# UCPD_lamp.net
KiCad netlist of a schematic drawn in Altium Designer
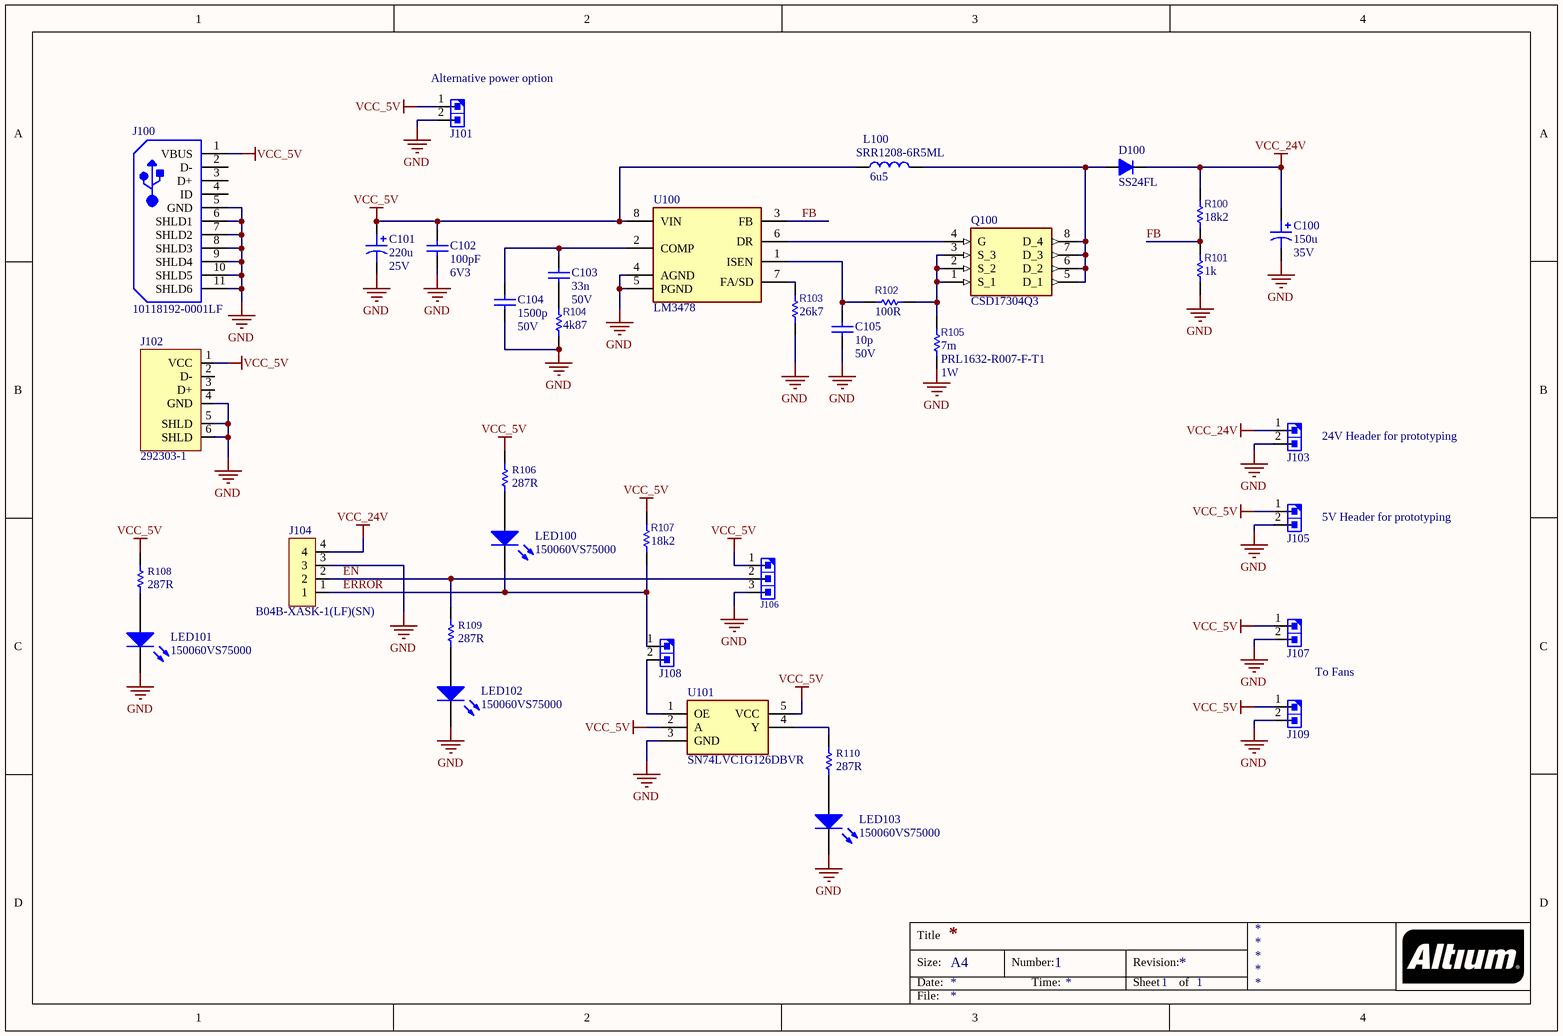
[diagram p0: UCPD_lamp.SchDoc]

(export (version "E")
  (design (tool "Eeschema 10.0.6"))
  (components
    (comp (ref "C100")
      (value "150u")
      (footprint "CAPAE1030X1050N")
      (description "CAP ALUM POLY HYB 150UF 35V SMD")
      (fields
        (field (name "MANUFACTURER") "Panasonic")
        (field (name "MANUFACTURER PART NUMBER") "EEH-ZA1V151P")
        (field (name "VOLTAGE") "35V")
      )
      (libsource (lib "UCPD_capacitors") (part "EEH-ZA1V151P"))
    )
    (comp (ref "C101")
      (value "220u")
      (footprint "CAPAE1030X1050N")
      (description "CAP ALUM 220UF 20% 25V SMD")
      (fields
        (field (name "MANUFACTURER") "Nichicon")
        (field (name "MANUFACTURER PART NUMBER") "UUD1E221MNL1GS")
        (field (name "VOLTAGE") "25V")
      )
      (libsource (lib "UCPD_capacitors") (part "UUD1E221MNL1GS"))
    )
    (comp (ref "C102")
      (value "100pF")
      (footprint "CAPC1005X06N")
      (description "CAP CER 0.1UF 6.3V X7R 0402")
      (fields
        (field (name "MANUFACTURER PART NUMBER") "GRM155R70J104KA01D")
        (field (name "MANUFACTURER") "Murata")
        (field (name "VOLTAGE") "6V3")
      )
      (libsource (lib "UCPD_capacitors") (part "GRM155R70J104KA01D"))
    )
    (comp (ref "C103")
      (value "33n")
      (footprint "CAPC2012X14N")
      (description "CAP CER 0.033UF 50V C0G 0805")
      (fields
        (field (name "MANUFACTURER PART NUMBER") "CGA4J2C0G1H333J125AA")
        (field (name "MANUFACTURER") "TDK")
        (field (name "VOLTAGE") "50V")
      )
      (libsource (lib "UCPD_capacitors") (part "CGA4J2C0G1H333J125AA"))
    )
    (comp (ref "C104")
      (value "1500p")
      (footprint "CAPC2012X14N")
      (description "CAP CER 1500PF 50V C0G 0805")
      (fields
        (field (name "MANUFACTURER PART NUMBER") "C2012C0G1H152J060AA")
        (field (name "MANUFACTURER") "TDK")
        (field (name "VOLTAGE") "50V")
      )
      (libsource (lib "UCPD_capacitors") (part "C2012C0G1H152J060AA"))
    )
    (comp (ref "C105")
      (value "10p")
      (footprint "CAPC2012X14N")
      (description "CAP CER 10PF 50V C0G/NP0 0805")
      (fields
        (field (name "MANUFACTURER PART NUMBER") "08055A100JAT2A")
        (field (name "MANUFACTURER") "AVX")
        (field (name "VOLTAGE") "50V")
      )
      (libsource (lib "UCPD_capacitors") (part "08055A100JAT2A"))
    )
    (comp (ref "D100")
      (value "SS24FL")
      (footprint "SOD-123FL")
      (description "DIODE SCHOTTKY 40V 2A SOD123F")
      (fields (field (name "MANUFACTURER") "ON Semiconductor"))
      (libsource (lib "UCPD") (part "SS24FL"))
    )
    (comp (ref "J100")
      (value "10118192-0001LF")
      (footprint "10118192-0001LF")
      (description "CONN Micro USB B Type Receptacle")
      (fields (field (name "MANUFACTURER") "FCI"))
      (libsource (lib "UCPD") (part "10118192-0001LF"))
    )
    (comp (ref "J101")
      (value "PRPC002SAAN-RC")
      (footprint "HDR_1x2_0.100\"")
      (description "CONN HEADER VERT 2POS 2.54MM")
      (fields (field (name "MANUFACTURER") "Sullins"))
      (libsource (lib "UCPD") (part "PRPC002SAAN-RC"))
    )
    (comp (ref "J102")
      (value "292303-1")
      (footprint "292303-1")
      (description "CONN USB2.0 TYPEA 4POS R/A")
      (fields (field (name "MANUFACTURER") "TE Connectivity"))
      (libsource (lib "UCPD") (part "292303-1"))
    )
    (comp (ref "J103")
      (value "PRPC002SAAN-RC")
      (footprint "HDR_1x2_0.100\"")
      (description "CONN HEADER VERT 2POS 2.54MM")
      (fields (field (name "MANUFACTURER") "Sullins"))
      (libsource (lib "UCPD") (part "PRPC002SAAN-RC"))
    )
    (comp (ref "J104")
      (value "B04B-XASK-1(LF)(SN)")
      (footprint "B04B-XASK-1(LF)(SN)")
      (description "CONN HEADER VERT 4POS 2.5MM")
      (fields (field (name "MANUFACTURER") "JST"))
      (libsource (lib "UCPD") (part "B04B-XASK-1(LF)(SN)"))
    )
    (comp (ref "J105")
      (value "PRPC002SAAN-RC")
      (footprint "HDR_1x2_0.100\"")
      (description "CONN HEADER VERT 2POS 2.54MM")
      (fields (field (name "MANUFACTURER") "Sullins"))
      (libsource (lib "UCPD") (part "PRPC002SAAN-RC"))
    )
    (comp (ref "J106")
      (value "PRPC003SAAN-RC")
      (footprint "HDR 3x1 0.100\"")
      (description "CONN HEADER VERT 3POS 2.54MM")
      (fields (field (name "MANUFACTURER") "Sullins"))
      (libsource (lib "UCPD") (part "PRPC003SAAN-RC"))
    )
    (comp (ref "J107")
      (value "PRPC002SAAN-RC")
      (footprint "HDR_1x2_0.100\"")
      (description "CONN HEADER VERT 2POS 2.54MM")
      (fields (field (name "MANUFACTURER") "Sullins"))
      (libsource (lib "UCPD") (part "PRPC002SAAN-RC"))
    )
    (comp (ref "J108")
      (value "PRPC002SAAN-RC")
      (footprint "HDR_1x2_0.100\"")
      (description "CONN HEADER VERT 2POS 2.54MM")
      (fields (field (name "MANUFACTURER") "Sullins"))
      (libsource (lib "UCPD") (part "PRPC002SAAN-RC"))
    )
    (comp (ref "J109")
      (value "PRPC002SAAN-RC")
      (footprint "HDR_1x2_0.100\"")
      (description "CONN HEADER VERT 2POS 2.54MM")
      (fields (field (name "MANUFACTURER") "Sullins"))
      (libsource (lib "UCPD") (part "PRPC002SAAN-RC"))
    )
    (comp (ref "L100")
      (value "6u5")
      (footprint "INDPM127127X850N")
      (description "FIXED IND 6.5UH 6A 18 MOHM SMD")
      (fields
        (field (name "MANUFACTURER") "Bourns")
        (field (name "MANUFACTURER PART NUMBER") "SRR1208-6R5ML")
        (field (name "Comment") "SRR1208-6R5ML")
      )
      (libsource (lib "UCPD") (part "SRR1208-6R5ML"))
    )
    (comp (ref "LED100")
      (value "150060VS75000")
      (footprint "0603_A")
      (description "SMD mono-color Chip LED, WL-SMCW, Bright Green")
      (fields
        (field (name "MANUFACTURER") "Wuerth Elektronik")
        (field (name "DISTRIBUTOR PART NUMBER") "732-4980-1-ND")
      )
      (libsource (lib "Altium Content Vault") (part "WE-LED_K1A2-2"))
    )
    (comp (ref "LED101")
      (value "150060VS75000")
      (footprint "0603_A")
      (description "SMD mono-color Chip LED, WL-SMCW, Bright Green")
      (fields
        (field (name "MANUFACTURER") "Wuerth Elektronik")
        (field (name "DISTRIBUTOR PART NUMBER") "732-4980-1-ND")
      )
      (libsource (lib "Altium Content Vault") (part "WE-LED_K1A2-2"))
    )
    (comp (ref "LED102")
      (value "150060VS75000")
      (footprint "0603_A")
      (description "SMD mono-color Chip LED, WL-SMCW, Bright Green")
      (fields
        (field (name "MANUFACTURER") "Wuerth Elektronik")
        (field (name "DISTRIBUTOR PART NUMBER") "732-4980-1-ND")
      )
      (libsource (lib "Altium Content Vault") (part "WE-LED_K1A2-2"))
    )
    (comp (ref "LED103")
      (value "150060VS75000")
      (footprint "0603_A")
      (description "SMD mono-color Chip LED, WL-SMCW, Bright Green")
      (fields
        (field (name "MANUFACTURER") "Wuerth Elektronik")
        (field (name "DISTRIBUTOR PART NUMBER") "732-4980-1-ND")
      )
      (libsource (lib "Altium Content Vault") (part "WE-LED_K1A2-2"))
    )
    (comp (ref "Q100")
      (value "CSD17304Q3")
      (footprint "SamacSys:DQG_VSON-CLIP")
      (description "MOSFET (N-Channel)")
      (fields (field (name "MOUSER PART NUMBER") "595-CSD17304Q3"))
      (libsource (lib "*") (part "CSD17304Q3"))
    )
    (comp (ref "R100")
      (value "18k2")
      (footprint "RESC1005X03N")
      (description "RES SMD 18.2K OHM 1% 1/16W 0402")
      (fields
        (field (name "MANUFACTURER") "Vishay Dale")
        (field (name "MANUFACTURER PART NUMBER") "CRCW040218K2FKED")
      )
      (libsource (lib "UCPD_resistors") (part "CRCW040218K2FKED"))
    )
    (comp (ref "R101")
      (value "1k")
      (footprint "RESC1005X03N")
      (description "RES SMD 1K OHM 1% 1/16W 0402")
      (fields
        (field (name "MANUFACTURER") "Vishay Dale")
        (field (name "MANUFACTURER PART NUMBER") "CRCW04021K00FKEDC")
      )
      (libsource (lib "UCPD_resistors") (part "CRCW04021K00FKEDC"))
    )
    (comp (ref "R102")
      (value "100R")
      (footprint "RESC1005X03N")
      (description "RES SMD 100 OHM 1% 1/16W 0402")
      (fields
        (field (name "MANUFACTURER") "Vishay Dale")
        (field (name "MANUFACTURER PART NUMBER") "CRCW0402100RFKEDC")
      )
      (libsource (lib "UCPD_resistors") (part "CRCW0402100RFKEDC"))
    )
    (comp (ref "R103")
      (value "26k7")
      (footprint "RESC1005X03N")
      (description "RES SMD 26.7K OHM 1% 1/16W 0402")
      (fields
        (field (name "MANUFACTURER") "Vishay Dale")
        (field (name "MANUFACTURER PART NUMBER") "CRCW040226K7FKED")
      )
      (libsource (lib "UCPD_resistors") (part "CRCW040226K7FKED"))
    )
    (comp (ref "R104")
      (value "4k87")
      (footprint "RESC1005X03N")
      (description "RES SMD 4.87K OHM 1% 1/16W 0402")
      (fields
        (field (name "MANUFACTURER") "Vishay Dale")
        (field (name "MANUFACTURER PART NUMBER") "CRCW04024K87FKED")
      )
      (libsource (lib "UCPD_resistors") (part "CRCW04024K87FKED"))
    )
    (comp (ref "R105")
      (value "7m")
      (footprint "RESC1632X60N")
      (description "RES 0.007 OHM 1W 1206 WIDE")
      (fields
        (field (name "MANUFACTURER") "Susumu")
        (field (name "MANUFACTURER PART NUMBER") "PRL1632-R007-F-T1")
        (field (name "POWER") "1W")
        (field (name "Comment") "PRL1632-R007-F-T1")
      )
      (libsource (lib "UCPD_resistors") (part "PRL1632-R007-F-T1"))
    )
    (comp (ref "R106")
      (value "287R")
      (footprint "RESC1005X03N")
      (fields
        (field (name "MANUFACTURER") "Yageo")
        (field (name "MANUFACTURER PART NUMBER") "YAG3089CT-ND")
        (field (name "Comment") "RES: GENERAL")
      )
      (libsource (lib "UCPD_resistors") (part "RES{colon} GENERAL"))
    )
    (comp (ref "R107")
      (value "18k2")
      (footprint "RESC1005X03N")
      (description "RES SMD 18.2K OHM 1% 1/16W 0402")
      (fields
        (field (name "MANUFACTURER") "Vishay Dale")
        (field (name "MANUFACTURER PART NUMBER") "CRCW040218K2FKED")
      )
      (libsource (lib "UCPD_resistors") (part "CRCW040218K2FKED"))
    )
    (comp (ref "R108")
      (value "287R")
      (footprint "RESC1005X03N")
      (fields
        (field (name "MANUFACTURER") "Yageo")
        (field (name "MANUFACTURER PART NUMBER") "YAG3089CT-ND")
        (field (name "Comment") "RES: GENERAL")
      )
      (libsource (lib "UCPD_resistors") (part "RES{colon} GENERAL"))
    )
    (comp (ref "R109")
      (value "287R")
      (footprint "RESC1005X03N")
      (fields
        (field (name "MANUFACTURER") "Yageo")
        (field (name "MANUFACTURER PART NUMBER") "YAG3089CT-ND")
        (field (name "Comment") "RES: GENERAL")
      )
      (libsource (lib "UCPD_resistors") (part "RES{colon} GENERAL"))
    )
    (comp (ref "R110")
      (value "287R")
      (footprint "RESC1005X03N")
      (fields
        (field (name "MANUFACTURER") "Yageo")
        (field (name "MANUFACTURER PART NUMBER") "YAG3089CT-ND")
        (field (name "Comment") "RES: GENERAL")
      )
      (libsource (lib "UCPD_resistors") (part "RES{colon} GENERAL"))
    )
    (comp (ref "U100")
      (value "LM3478")
      (footprint "SOIC127P600X175-8N")
      (description "IC REG CTRLR MULT TOPOLOGY 8SOIC")
      (fields
        (field (name "MANUFACTURER") "Texas Instruments")
        (field (name "MANUFACTURER PART NUMBER") "LM3478MAX/NOPB")
      )
      (libsource (lib "UCPD") (part "LM3478"))
    )
    (comp (ref "U101")
      (value "SN74LVC1G126DBVR")
      (footprint "SOT95P280X145-5N")
      (description "IC BUF NON-INVERT 5.5V SOT23-5")
      (fields
        (field (name "MANUFACTURER") "Texas Instruments")
        (field (name "MOUSER PART NUMBER") "595-SN74LVC1G126DBVR")
      )
      (libsource (lib "UCPD") (part "SN74LVC1G126DBVR"))
    )
  )
  (nets
    (net (code "1") (name "/EN") (class "Default")
      (node (ref "J104") (pin "2") (pinfunction "2_2") (pintype "passive"))
      (node (ref "J106") (pin "2") (pinfunction "2_2") (pintype "passive"))
      (node (ref "R109") (pin "2") (pinfunction "2_2") (pintype "passive"))
    )
    (net (code "2") (name "/ERROR") (class "Default")
      (node (ref "J104") (pin "1") (pinfunction "1_1") (pintype "passive"))
      (node (ref "J108") (pin "1") (pinfunction "1_1") (pintype "passive"))
      (node (ref "LED100") (pin "1") (pinfunction "K_1") (pintype "passive"))
      (node (ref "R107") (pin "1") (pinfunction "1_1") (pintype "passive"))
    )
    (net (code "3") (name "/FB") (class "Default")
      (node (ref "R100") (pin "1") (pinfunction "1_1") (pintype "passive"))
      (node (ref "R101") (pin "2") (pinfunction "2_2") (pintype "passive"))
      (node (ref "U100") (pin "3") (pinfunction "FB_3") (pintype "passive"))
    )
    (net (code "4") (name "GND") (class "Default")
      (node (ref "C100") (pin "2") (pinfunction "2_2") (pintype "passive"))
      (node (ref "C101") (pin "2") (pinfunction "2_2") (pintype "passive"))
      (node (ref "C102") (pin "1") (pinfunction "1_1") (pintype "passive"))
      (node (ref "C104") (pin "1") (pinfunction "1_1") (pintype "passive"))
      (node (ref "C105") (pin "1") (pinfunction "1_1") (pintype "passive"))
      (node (ref "J100") (pin "10") (pinfunction "SHLD5_10") (pintype "passive"))
      (node (ref "J100") (pin "11") (pinfunction "SHLD6_11") (pintype "passive"))
      (node (ref "J100") (pin "5") (pinfunction "GND_5") (pintype "passive"))
      (node (ref "J100") (pin "6") (pinfunction "SHLD1_6") (pintype "passive"))
      (node (ref "J100") (pin "7") (pinfunction "SHLD2_7") (pintype "passive"))
      (node (ref "J100") (pin "8") (pinfunction "SHLD3_8") (pintype "passive"))
      (node (ref "J100") (pin "9") (pinfunction "SHLD4_9") (pintype "passive"))
      (node (ref "J101") (pin "2") (pinfunction "2_2") (pintype "passive"))
      (node (ref "J102") (pin "4") (pinfunction "GND_4") (pintype "passive"))
      (node (ref "J102") (pin "5") (pinfunction "SHLD_5") (pintype "passive"))
      (node (ref "J102") (pin "6") (pinfunction "SHLD_6") (pintype "passive"))
      (node (ref "J103") (pin "2") (pinfunction "2_2") (pintype "passive"))
      (node (ref "J104") (pin "3") (pinfunction "3_3") (pintype "passive"))
      (node (ref "J105") (pin "2") (pinfunction "2_2") (pintype "passive"))
      (node (ref "J106") (pin "3") (pinfunction "3_3") (pintype "passive"))
      (node (ref "J107") (pin "2") (pinfunction "2_2") (pintype "passive"))
      (node (ref "J109") (pin "2") (pinfunction "2_2") (pintype "passive"))
      (node (ref "LED101") (pin "1") (pinfunction "K_1") (pintype "passive"))
      (node (ref "LED102") (pin "1") (pinfunction "K_1") (pintype "passive"))
      (node (ref "LED103") (pin "1") (pinfunction "K_1") (pintype "passive"))
      (node (ref "R101") (pin "1") (pinfunction "1_1") (pintype "passive"))
      (node (ref "R103") (pin "1") (pinfunction "1_1") (pintype "passive"))
      (node (ref "R104") (pin "1") (pinfunction "1_1") (pintype "passive"))
      (node (ref "R105") (pin "1") (pinfunction "1_1") (pintype "passive"))
      (node (ref "U100") (pin "4") (pinfunction "AGND_4") (pintype "passive"))
      (node (ref "U100") (pin "5") (pinfunction "PGND_5") (pintype "passive"))
      (node (ref "U101") (pin "3") (pinfunction "GND_3") (pintype "passive"))
    )
    (net (code "5") (name "Net-(C103-Pad1)") (class "Default")
      (node (ref "C103") (pin "1") (pinfunction "1_1") (pintype "passive"))
      (node (ref "R104") (pin "2") (pinfunction "2_2") (pintype "passive"))
    )
    (net (code "6") (name "Net-(D100-A)") (class "Default")
      (node (ref "D100") (pin "1") (pinfunction "A_1") (pintype "passive"))
      (node (ref "L100") (pin "2") (pinfunction "2_2") (pintype "passive"))
      (node (ref "Q100") (pin "5") (pinfunction "D_1_5") (pintype "output"))
      (node (ref "Q100") (pin "6") (pinfunction "D_2_6") (pintype "output"))
      (node (ref "Q100") (pin "7") (pinfunction "D_3_7") (pintype "output"))
      (node (ref "Q100") (pin "8") (pinfunction "D_4_8") (pintype "output"))
    )
    (net (code "7") (name "Net-(LED100-A)") (class "Default")
      (node (ref "LED100") (pin "2") (pinfunction "A_2") (pintype "passive"))
      (node (ref "R106") (pin "1") (pinfunction "1_1") (pintype "passive"))
    )
    (net (code "8") (name "Net-(LED101-A)") (class "Default")
      (node (ref "LED101") (pin "2") (pinfunction "A_2") (pintype "passive"))
      (node (ref "R108") (pin "1") (pinfunction "1_1") (pintype "passive"))
    )
    (net (code "9") (name "Net-(LED102-A)") (class "Default")
      (node (ref "LED102") (pin "2") (pinfunction "A_2") (pintype "passive"))
      (node (ref "R109") (pin "1") (pinfunction "1_1") (pintype "passive"))
    )
    (net (code "10") (name "Net-(LED103-A)") (class "Default")
      (node (ref "LED103") (pin "2") (pinfunction "A_2") (pintype "passive"))
      (node (ref "R110") (pin "1") (pinfunction "1_1") (pintype "passive"))
    )
    (net (code "11") (name "Net-(Q100-G)") (class "Default")
      (node (ref "Q100") (pin "4") (pinfunction "G_4") (pintype "input"))
      (node (ref "U100") (pin "6") (pinfunction "DR_6") (pintype "passive"))
    )
    (net (code "12") (name "Net-(Q100-S_1)") (class "Default")
      (node (ref "Q100") (pin "1") (pinfunction "S_1_1") (pintype "input"))
      (node (ref "Q100") (pin "2") (pinfunction "S_2_2") (pintype "input"))
      (node (ref "Q100") (pin "3") (pinfunction "S_3_3") (pintype "input"))
      (node (ref "R102") (pin "2") (pinfunction "2_2") (pintype "passive"))
      (node (ref "R105") (pin "2") (pinfunction "2_2") (pintype "passive"))
    )
    (net (code "13") (name "Net-(U100-COMP)") (class "Default")
      (node (ref "C103") (pin "2") (pinfunction "2_2") (pintype "passive"))
      (node (ref "C104") (pin "2") (pinfunction "2_2") (pintype "passive"))
      (node (ref "U100") (pin "2") (pinfunction "COMP_2") (pintype "passive"))
    )
    (net (code "14") (name "Net-(U100-FA{slash}SD)") (class "Default")
      (node (ref "R103") (pin "2") (pinfunction "2_2") (pintype "passive"))
      (node (ref "U100") (pin "7") (pinfunction "FA/SD_7") (pintype "passive"))
    )
    (net (code "15") (name "Net-(U100-ISEN)") (class "Default")
      (node (ref "C105") (pin "2") (pinfunction "2_2") (pintype "passive"))
      (node (ref "R102") (pin "1") (pinfunction "1_1") (pintype "passive"))
      (node (ref "U100") (pin "1") (pinfunction "ISEN_1") (pintype "passive"))
    )
    (net (code "16") (name "Net-(U101-OE)") (class "Default")
      (node (ref "J108") (pin "2") (pinfunction "2_2") (pintype "passive"))
      (node (ref "U101") (pin "1") (pinfunction "OE_1") (pintype "passive"))
    )
    (net (code "17") (name "Net-(U101-Y)") (class "Default")
      (node (ref "R110") (pin "2") (pinfunction "2_2") (pintype "passive"))
      (node (ref "U101") (pin "4") (pinfunction "Y_4") (pintype "passive"))
    )
    (net (code "18") (name "VCC_5V") (class "Default")
      (node (ref "C101") (pin "1") (pinfunction "1_1") (pintype "passive"))
      (node (ref "C102") (pin "2") (pinfunction "2_2") (pintype "passive"))
      (node (ref "J100") (pin "1") (pinfunction "VBUS_1") (pintype "passive"))
      (node (ref "J101") (pin "1") (pinfunction "1_1") (pintype "passive"))
      (node (ref "J102") (pin "1") (pinfunction "VCC_1") (pintype "passive"))
      (node (ref "J105") (pin "1") (pinfunction "1_1") (pintype "passive"))
      (node (ref "J106") (pin "1") (pinfunction "1_1") (pintype "passive"))
      (node (ref "J107") (pin "1") (pinfunction "1_1") (pintype "passive"))
      (node (ref "J109") (pin "1") (pinfunction "1_1") (pintype "passive"))
      (node (ref "L100") (pin "1") (pinfunction "1_1") (pintype "passive"))
      (node (ref "R106") (pin "2") (pinfunction "2_2") (pintype "passive"))
      (node (ref "R107") (pin "2") (pinfunction "2_2") (pintype "passive"))
      (node (ref "R108") (pin "2") (pinfunction "2_2") (pintype "passive"))
      (node (ref "U100") (pin "8") (pinfunction "VIN_8") (pintype "passive"))
      (node (ref "U101") (pin "2") (pinfunction "A_2") (pintype "passive"))
      (node (ref "U101") (pin "5") (pinfunction "VCC_5") (pintype "passive"))
    )
    (net (code "19") (name "VCC_24V") (class "Default")
      (node (ref "C100") (pin "1") (pinfunction "1_1") (pintype "passive"))
      (node (ref "D100") (pin "2") (pinfunction "K_2") (pintype "passive"))
      (node (ref "J103") (pin "1") (pinfunction "1_1") (pintype "passive"))
      (node (ref "J104") (pin "4") (pinfunction "4_4") (pintype "passive"))
      (node (ref "R100") (pin "2") (pinfunction "2_2") (pintype "passive"))
    )
    (net (code "20") (name "unconnected-(J100-D+-Pad3)") (class "Default")
      (node (ref "J100") (pin "3") (pinfunction "D+_3") (pintype "passive"))
    )
    (net (code "21") (name "unconnected-(J100-D--Pad2)") (class "Default")
      (node (ref "J100") (pin "2") (pinfunction "D-_2") (pintype "passive"))
    )
    (net (code "22") (name "unconnected-(J100-ID-Pad4)") (class "Default")
      (node (ref "J100") (pin "4") (pinfunction "ID_4") (pintype "passive"))
    )
    (net (code "23") (name "unconnected-(J102-D+-Pad3)") (class "Default")
      (node (ref "J102") (pin "3") (pinfunction "D+_3") (pintype "passive"))
    )
    (net (code "24") (name "unconnected-(J102-D--Pad2)") (class "Default")
      (node (ref "J102") (pin "2") (pinfunction "D-_2") (pintype "passive"))
    )
  )
)
